# MotorCircuit.net
KiCad netlist of a schematic drawn in Altium Designer
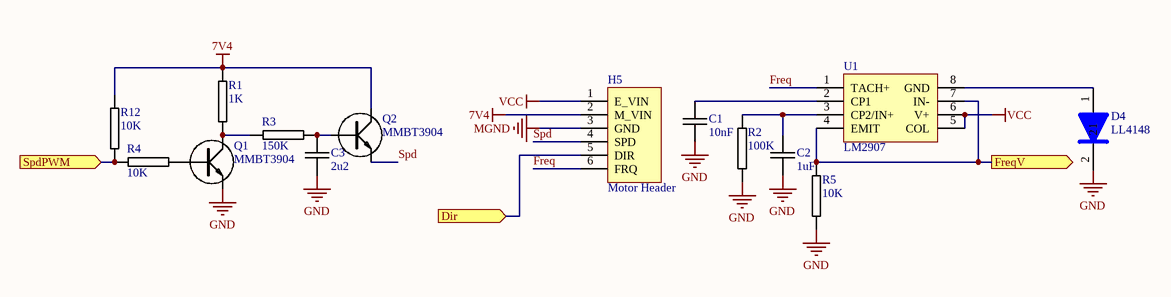
[diagram p0: MotorCircuit.SchDoc]

(export (version "E")
  (design (tool "Eeschema 10.0.6"))
  (components
    (comp (ref "C1")
      (value "10nF")
      (footprint "0805C-TBD")
      (description "CAPACITOR 0805 CERAMIC")
      (libsource (lib "vh_altium_library") (part "0805C-100nF-25V-X7R-MUR"))
    )
    (comp (ref "C2")
      (value "1uF")
      (footprint "0805C-GENERIC")
      (description "CAPACITOR 0805 CERAMIC")
      (fields (field (name "TOLERANCE") "±20%") (field (name "MANUFACTURER") "Panasonic - ECG"))
      (libsource (lib "vh_altium_library") (part "0805C-10UF-6V3-X5R-PAN"))
    )
    (comp (ref "C3")
      (value "2u2")
      (footprint "0805C-GENERIC")
      (description "CAPACITOR 0805 CERAMIC")
      (fields
        (field (name "MANUFACTURER PART NUMBER") "ECJ-1VB0J225K")
        (field (name "MANUFACTURER") "Panasonic - ECG")
      )
      (libsource (lib "vh_altium_library") (part "0805C-2U2-6V3-X5R-PAN"))
    )
    (comp (ref "D4")
      (value "LL4148")
      (footprint "LL4148")
      (description "Signal Diode")
      (libsource (lib "SupportComponents") (part "LL4148"))
    )
    (comp (ref "H5")
      (value "Motor Header")
      (footprint "Motor Header")
      (libsource (lib "SupportComponents") (part "Motor Header"))
    )
    (comp (ref "Q1")
      (value "MMBT3904")
      (footprint "SOT23-BCE")
      (description "BC847 SMALL SIGNAL NPN TRANSISTOR")
      (libsource (lib "vh_altium_library") (part "MMBT2222"))
    )
    (comp (ref "Q2")
      (value "MMBT3904")
      (footprint "SOT23-BCE")
      (description "BC847 SMALL SIGNAL NPN TRANSISTOR")
      (libsource (lib "vh_altium_library") (part "MMBT2222"))
    )
    (comp (ref "R1")
      (value "1K")
      (footprint "0805R-1K")
      (description "RESISTOR 0805 1/4 WATT THIN FILM")
      (libsource (lib "vh_altium_library") (part "0805R-1K"))
    )
    (comp (ref "R2")
      (value "100K")
      (footprint "0805R-100K")
      (description "RESISTOR 0805 1/4 WATT THIN FILM")
      (libsource (lib "vh_altium_library") (part "0805R-100K"))
    )
    (comp (ref "R3")
      (value "150K")
      (footprint "0805R-150K")
      (description "RESISTOR 0805 1/4 WATT THIN FILM")
      (libsource (lib "vh_altium_library") (part "0805R-150K"))
    )
    (comp (ref "R4")
      (value "10K")
      (footprint "0805R-10K")
      (description "RESISTOR 0805 1/4 WATT THIN FILM")
      (libsource (lib "vh_altium_library") (part "0805R-10K"))
    )
    (comp (ref "R5")
      (value "10K")
      (footprint "0805R-10K")
      (description "RESISTOR 0805 1/4 WATT THIN FILM")
      (libsource (lib "vh_altium_library") (part "0805R-10K"))
    )
    (comp (ref "R12")
      (value "10K")
      (footprint "0805R-10K")
      (description "RESISTOR 0805 1/4 WATT THIN FILM")
      (libsource (lib "vh_altium_library") (part "0805R-10K"))
    )
    (comp (ref "U1")
      (value "LM2907")
      (footprint "LM2907")
      (description "Freq to Voltage Converter")
      (libsource (lib "SupportComponents") (part "LM2907"))
    )
  )
  (nets
    (net (code "1") (name "/Dir") (class "Default")
      (node (ref "H5") (pin "5") (pinfunction "DIR_5") (pintype "passive"))
    )
    (net (code "2") (name "/Freq") (class "Default")
      (node (ref "H5") (pin "6") (pinfunction "FRQ_6") (pintype "passive"))
      (node (ref "U1") (pin "1") (pinfunction "TACH+_1") (pintype "passive"))
    )
    (net (code "3") (name "/FreqV") (class "Default")
      (node (ref "R5") (pin "1") (pintype "passive"))
      (node (ref "U1") (pin "4") (pinfunction "EMIT_4") (pintype "passive"))
      (node (ref "U1") (pin "7") (pinfunction "IN-_7") (pintype "passive"))
    )
    (net (code "4") (name "/Spd") (class "Default")
      (node (ref "H5") (pin "4") (pinfunction "SPD_4") (pintype "passive"))
      (node (ref "Q2") (pin "E") (pintype "passive"))
    )
    (net (code "5") (name "/SpdPWM") (class "Default")
      (node (ref "R12") (pin "1") (pintype "passive"))
      (node (ref "R4") (pin "1") (pintype "passive"))
    )
    (net (code "6") (name "7V4") (class "Default")
      (node (ref "H5") (pin "2") (pinfunction "M_VIN_2") (pintype "passive"))
      (node (ref "Q2") (pin "C") (pintype "passive"))
      (node (ref "R1") (pin "1") (pintype "passive"))
      (node (ref "R12") (pin "2") (pintype "passive"))
    )
    (net (code "7") (name "GND") (class "Default")
      (node (ref "C1") (pin "2") (pintype "passive"))
      (node (ref "C2") (pin "2") (pintype "passive"))
      (node (ref "C3") (pin "2") (pintype "passive"))
      (node (ref "D4") (pin "2") (pinfunction "2_2") (pintype "passive"))
      (node (ref "Q1") (pin "E") (pintype "passive"))
      (node (ref "R2") (pin "2") (pintype "passive"))
      (node (ref "R5") (pin "2") (pintype "passive"))
    )
    (net (code "8") (name "MGND") (class "Default")
      (node (ref "H5") (pin "3") (pinfunction "GND_3") (pintype "passive"))
    )
    (net (code "9") (name "Net-(C3-Pad1)") (class "Default")
      (node (ref "C3") (pin "1") (pintype "passive"))
      (node (ref "Q2") (pin "B") (pintype "passive"))
      (node (ref "R3") (pin "2") (pintype "passive"))
    )
    (net (code "10") (name "Net-(Q1-PadB)") (class "Default")
      (node (ref "Q1") (pin "B") (pintype "passive"))
      (node (ref "R4") (pin "2") (pintype "passive"))
    )
    (net (code "11") (name "Net-(Q1-PadC)") (class "Default")
      (node (ref "Q1") (pin "C") (pintype "passive"))
      (node (ref "R1") (pin "2") (pintype "passive"))
      (node (ref "R3") (pin "1") (pintype "passive"))
    )
    (net (code "12") (name "Net-(U1-CP1)") (class "Default")
      (node (ref "C1") (pin "1") (pintype "passive"))
      (node (ref "U1") (pin "2") (pinfunction "CP1_2") (pintype "passive"))
    )
    (net (code "13") (name "Net-(U1-CP2{slash}IN+)") (class "Default")
      (node (ref "C2") (pin "1") (pintype "passive"))
      (node (ref "R2") (pin "1") (pintype "passive"))
      (node (ref "U1") (pin "3") (pinfunction "CP2/IN+_3") (pintype "passive"))
    )
    (net (code "14") (name "Net-(U1-GND)") (class "Default")
      (node (ref "D4") (pin "1") (pinfunction "1_1") (pintype "passive"))
      (node (ref "U1") (pin "8") (pinfunction "GND_8") (pintype "passive"))
    )
    (net (code "15") (name "VCC") (class "Default")
      (node (ref "H5") (pin "1") (pinfunction "E_VIN_1") (pintype "passive"))
      (node (ref "U1") (pin "5") (pinfunction "COL_5") (pintype "passive"))
      (node (ref "U1") (pin "6") (pinfunction "V+_6") (pintype "passive"))
    )
  )
)
